# power_distribution_board_v4_final.net
KiCad netlist of a schematic drawn in EasyEDA
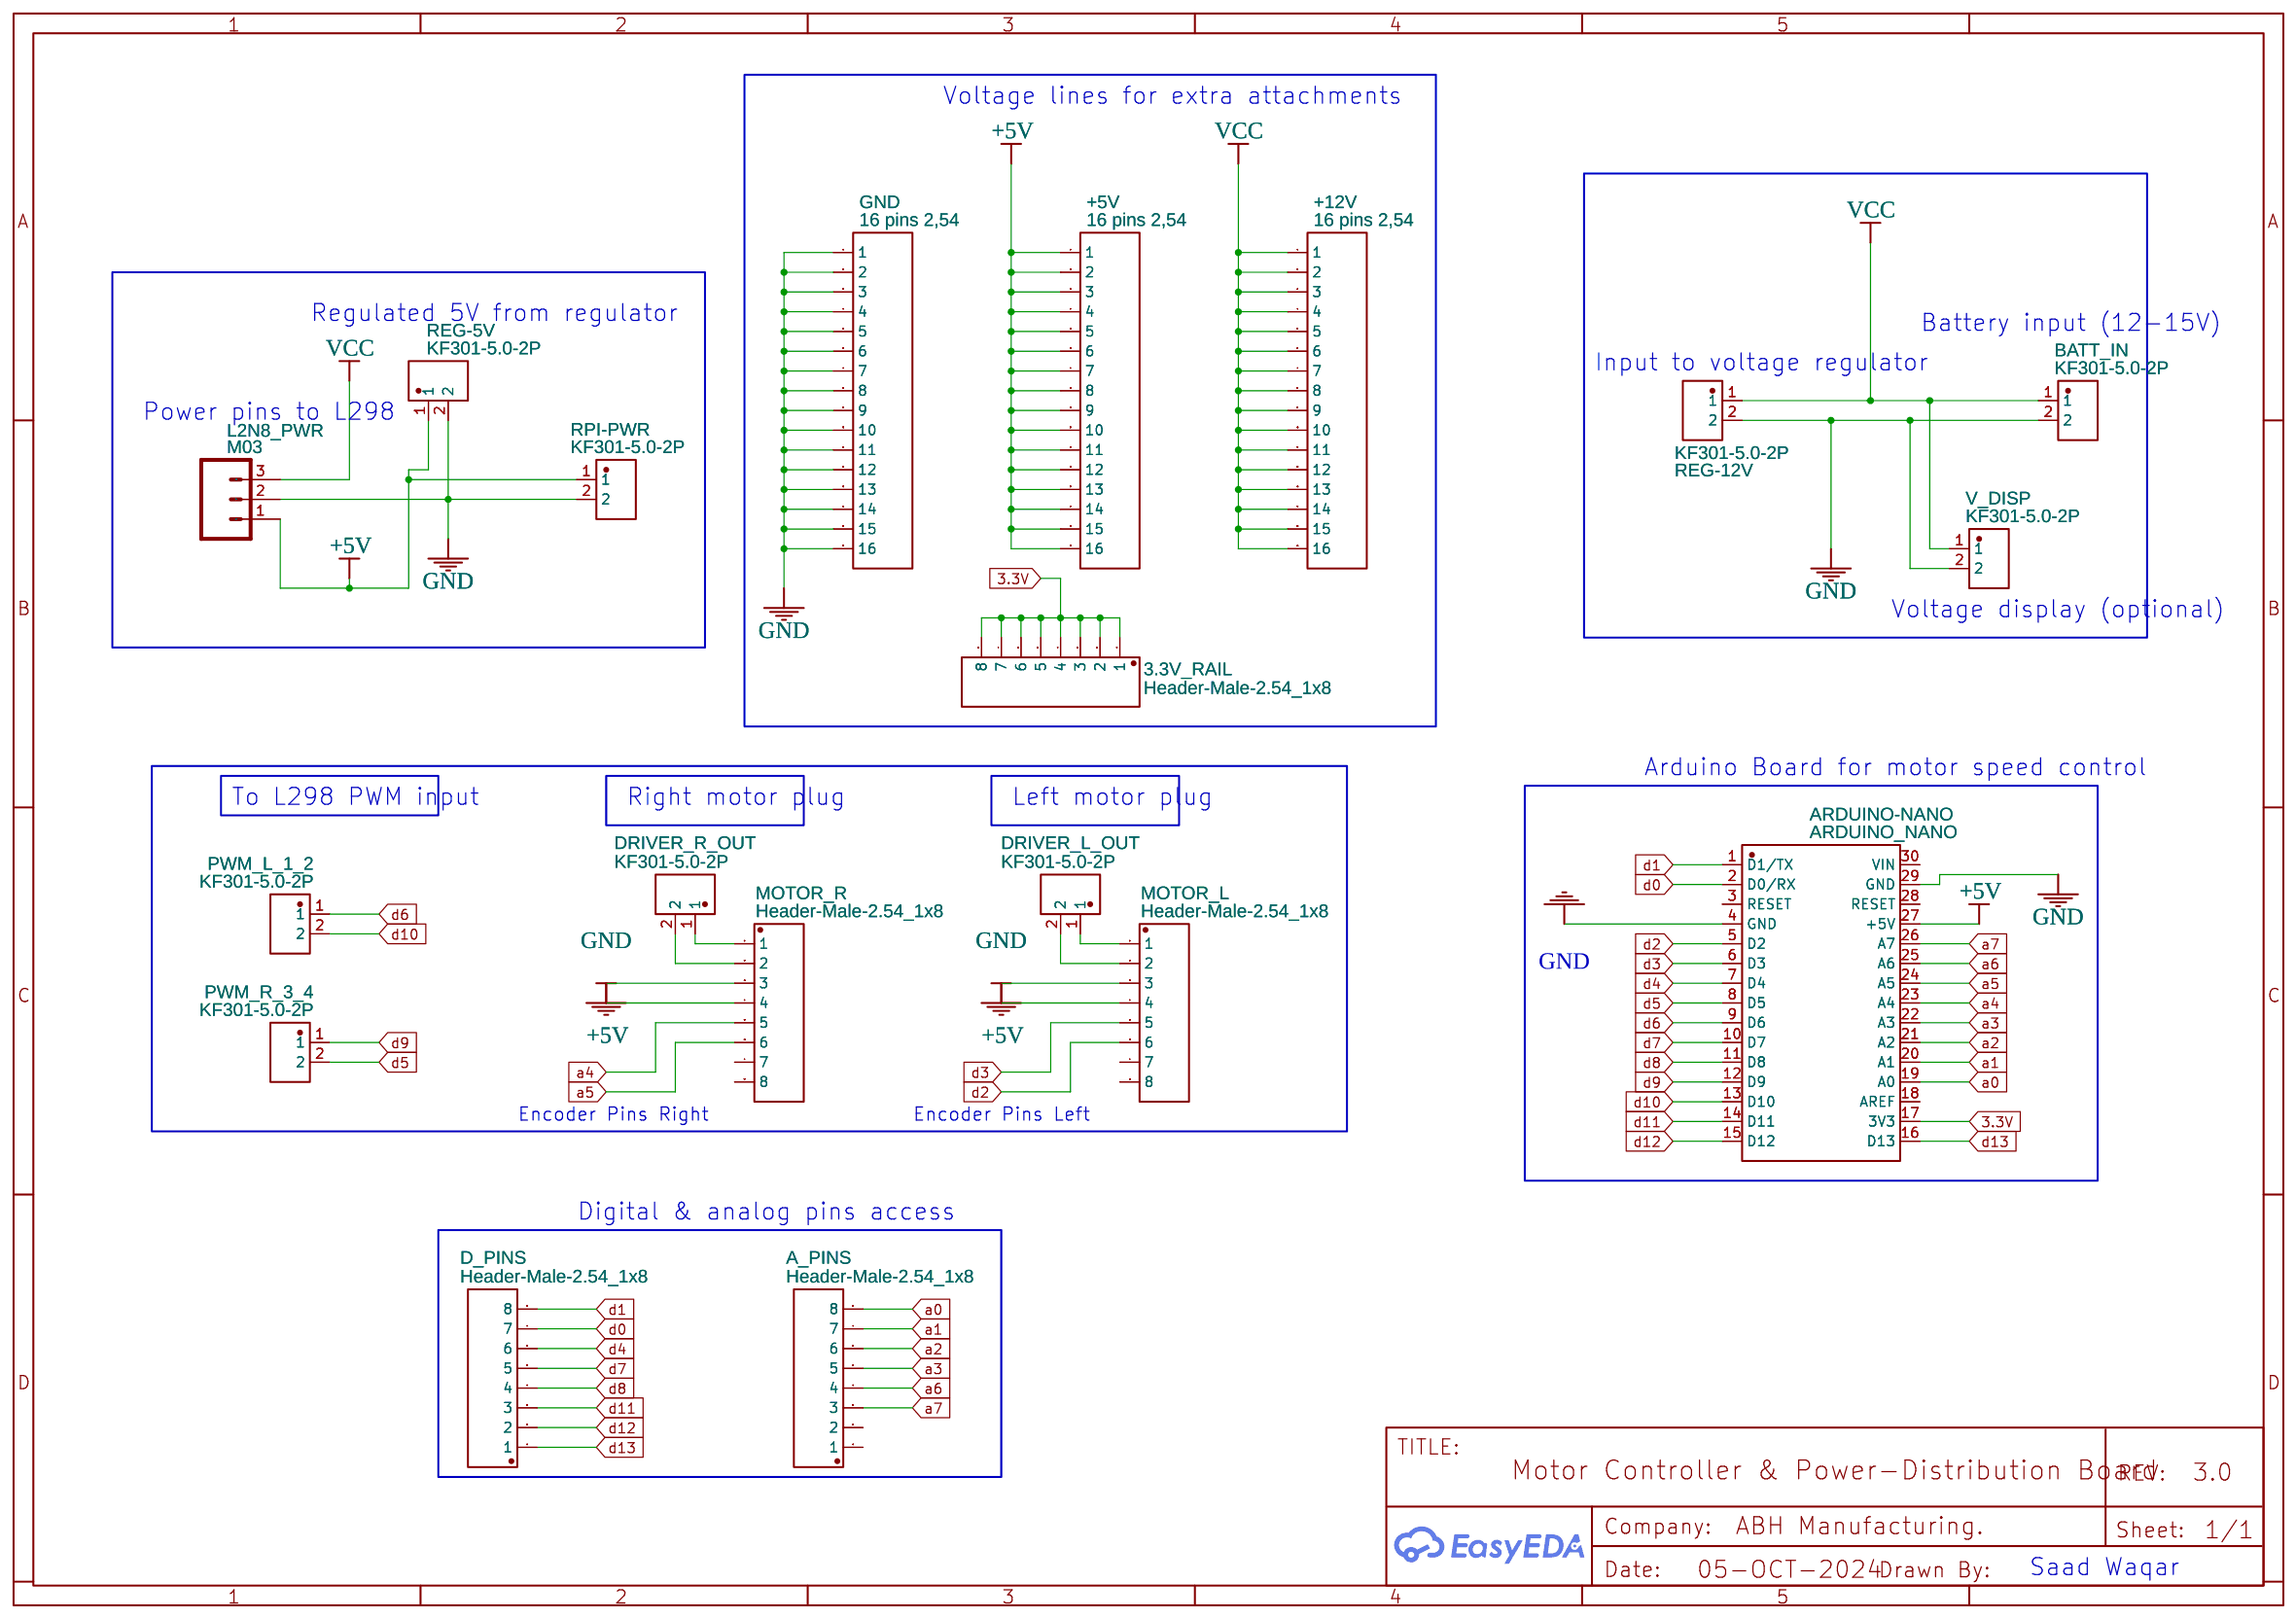
[diagram p0: schematic sheet]

(export (version "E")
  (design (tool "Eeschema 10.0.6"))
  (components
    (comp (ref "+5V") (value "16 pins 2,54") (libsource (lib "") (part "16 pins 2,54_2")))
    (comp (ref "+12V") (value "16 pins 2,54") (libsource (lib "") (part "16 pins 2,54_1")))
    (comp (ref "3.3V_RAIL")
      (value "Header-Male-2.54_1x8")
      (fields (field (name "Manufacturer Part") "B-2100S08P-A110") (field (name "Manufacturer") "Ckmtw(灿科盟)"))
      (libsource (lib "") (part "Header-Male-2.54_1x8_4"))
    )
    (comp (ref "ARDUINO-NANO") (value "ARDUINO_NANO") (libsource (lib "") (part "ARDUINO_NANO")))
    (comp (ref "A_PINS")
      (value "Header-Male-2.54_1x8")
      (fields (field (name "Manufacturer Part") "B-2100S08P-A110") (field (name "Manufacturer") "Ckmtw(灿科盟)"))
      (libsource (lib "") (part "Header-Male-2.54_1x8_1"))
    )
    (comp (ref "BATT_IN")
      (value "KF301-5.0-2P")
      (fields (field (name "Manufacturer") "KEFA(科发)"))
      (libsource (lib "") (part "KF301-5.0-2P_8"))
    )
    (comp (ref "DRIVER_L_OUT")
      (value "KF301-5.0-2P")
      (fields (field (name "Manufacturer") "KEFA(科发)"))
      (libsource (lib "") (part "KF301-5.0-2P_6"))
    )
    (comp (ref "DRIVER_R_OUT")
      (value "KF301-5.0-2P")
      (fields (field (name "Manufacturer") "KEFA(科发)"))
      (libsource (lib "") (part "KF301-5.0-2P"))
    )
    (comp (ref "D_PINS")
      (value "Header-Male-2.54_1x8")
      (fields (field (name "Manufacturer Part") "B-2100S08P-A110") (field (name "Manufacturer") "Ckmtw(灿科盟)"))
      (libsource (lib "") (part "Header-Male-2.54_1x8"))
    )
    (comp (ref "GND") (value "16 pins 2,54") (libsource (lib "") (part "16 pins 2,54")))
    (comp (ref "L2N8_PWR") (value "M03") (libsource (lib "") (part "M03")))
    (comp (ref "MOTOR_L")
      (value "Header-Male-2.54_1x8")
      (fields (field (name "Manufacturer Part") "B-2100S08P-A110") (field (name "Manufacturer") "Ckmtw(灿科盟)"))
      (libsource (lib "") (part "Header-Male-2.54_1x8_3"))
    )
    (comp (ref "MOTOR_R")
      (value "Header-Male-2.54_1x8")
      (fields (field (name "Manufacturer Part") "B-2100S08P-A110") (field (name "Manufacturer") "Ckmtw(灿科盟)"))
      (libsource (lib "") (part "Header-Male-2.54_1x8_2"))
    )
    (comp (ref "PWM_L_1_2")
      (value "KF301-5.0-2P")
      (fields (field (name "Manufacturer") "KEFA(科发)"))
      (libsource (lib "") (part "KF301-5.0-2P_7"))
    )
    (comp (ref "PWM_R_3_4")
      (value "KF301-5.0-2P")
      (fields (field (name "Manufacturer") "KEFA(科发)"))
      (libsource (lib "") (part "KF301-5.0-2P_3"))
    )
    (comp (ref "REG-5V")
      (value "KF301-5.0-2P")
      (fields (field (name "Manufacturer") "KEFA(科发)"))
      (libsource (lib "") (part "KF301-5.0-2P_2"))
    )
    (comp (ref "REG-12V")
      (value "KF301-5.0-2P")
      (fields (field (name "Manufacturer") "KEFA(科发)"))
      (libsource (lib "") (part "KF301-5.0-2P_4"))
    )
    (comp (ref "RPI-PWR")
      (value "KF301-5.0-2P")
      (fields (field (name "Manufacturer") "KEFA(科发)"))
      (libsource (lib "") (part "KF301-5.0-2P_1"))
    )
    (comp (ref "V_DISP")
      (value "KF301-5.0-2P")
      (fields (field (name "Manufacturer") "KEFA(科发)"))
      (libsource (lib "") (part "KF301-5.0-2P_5"))
    )
  )
  (nets
    (net (code "1") (name "+5V") (class "Default")
      (node (ref "+5V") (pin "1") (pinfunction "1_1") (pintype "input"))
      (node (ref "+5V") (pin "10") (pinfunction "10_10") (pintype "input"))
      (node (ref "+5V") (pin "11") (pinfunction "11_11") (pintype "input"))
      (node (ref "+5V") (pin "12") (pinfunction "12_12") (pintype "input"))
      (node (ref "+5V") (pin "13") (pinfunction "13_13") (pintype "input"))
      (node (ref "+5V") (pin "14") (pinfunction "14_14") (pintype "input"))
      (node (ref "+5V") (pin "15") (pinfunction "15_15") (pintype "input"))
      (node (ref "+5V") (pin "16") (pinfunction "16_16") (pintype "input"))
      (node (ref "+5V") (pin "2") (pinfunction "2_2") (pintype "input"))
      (node (ref "+5V") (pin "3") (pinfunction "3_3") (pintype "input"))
      (node (ref "+5V") (pin "4") (pinfunction "4_4") (pintype "input"))
      (node (ref "+5V") (pin "5") (pinfunction "5_5") (pintype "input"))
      (node (ref "+5V") (pin "6") (pinfunction "6_6") (pintype "input"))
      (node (ref "+5V") (pin "7") (pinfunction "7_7") (pintype "input"))
      (node (ref "+5V") (pin "8") (pinfunction "8_8") (pintype "input"))
      (node (ref "+5V") (pin "9") (pinfunction "9_9") (pintype "input"))
      (node (ref "ARDUINO-NANO") (pin "27") (pinfunction "+5V_27") (pintype "unspecified"))
      (node (ref "L2N8_PWR") (pin "1") (pinfunction "1_1") (pintype "unspecified"))
      (node (ref "MOTOR_L") (pin "4") (pinfunction "4_4") (pintype "unspecified"))
      (node (ref "MOTOR_R") (pin "4") (pinfunction "4_4") (pintype "unspecified"))
      (node (ref "REG-5V") (pin "1") (pinfunction "1_1") (pintype "unspecified"))
      (node (ref "RPI-PWR") (pin "1") (pinfunction "1_1") (pintype "unspecified"))
    )
    (net (code "2") (name "3.3V") (class "Default")
      (node (ref "3.3V_RAIL") (pin "1") (pinfunction "1_1") (pintype "unspecified"))
      (node (ref "3.3V_RAIL") (pin "2") (pinfunction "2_2") (pintype "unspecified"))
      (node (ref "3.3V_RAIL") (pin "3") (pinfunction "3_3") (pintype "unspecified"))
      (node (ref "3.3V_RAIL") (pin "4") (pinfunction "4_4") (pintype "unspecified"))
      (node (ref "3.3V_RAIL") (pin "5") (pinfunction "5_5") (pintype "unspecified"))
      (node (ref "3.3V_RAIL") (pin "6") (pinfunction "6_6") (pintype "unspecified"))
      (node (ref "3.3V_RAIL") (pin "7") (pinfunction "7_7") (pintype "unspecified"))
      (node (ref "3.3V_RAIL") (pin "8") (pinfunction "8_8") (pintype "unspecified"))
      (node (ref "ARDUINO-NANO") (pin "17") (pinfunction "3V3_17") (pintype "unspecified"))
    )
    (net (code "3") (name "GND") (class "Default")
      (node (ref "ARDUINO-NANO") (pin "29") (pinfunction "GND_29") (pintype "unspecified"))
      (node (ref "ARDUINO-NANO") (pin "4") (pinfunction "GND_4") (pintype "unspecified"))
      (node (ref "BATT_IN") (pin "2") (pinfunction "2_2") (pintype "unspecified"))
      (node (ref "GND") (pin "1") (pinfunction "1_1") (pintype "input"))
      (node (ref "GND") (pin "10") (pinfunction "10_10") (pintype "input"))
      (node (ref "GND") (pin "11") (pinfunction "11_11") (pintype "input"))
      (node (ref "GND") (pin "12") (pinfunction "12_12") (pintype "input"))
      (node (ref "GND") (pin "13") (pinfunction "13_13") (pintype "input"))
      (node (ref "GND") (pin "14") (pinfunction "14_14") (pintype "input"))
      (node (ref "GND") (pin "15") (pinfunction "15_15") (pintype "input"))
      (node (ref "GND") (pin "16") (pinfunction "16_16") (pintype "input"))
      (node (ref "GND") (pin "2") (pinfunction "2_2") (pintype "input"))
      (node (ref "GND") (pin "3") (pinfunction "3_3") (pintype "input"))
      (node (ref "GND") (pin "4") (pinfunction "4_4") (pintype "input"))
      (node (ref "GND") (pin "5") (pinfunction "5_5") (pintype "input"))
      (node (ref "GND") (pin "6") (pinfunction "6_6") (pintype "input"))
      (node (ref "GND") (pin "7") (pinfunction "7_7") (pintype "input"))
      (node (ref "GND") (pin "8") (pinfunction "8_8") (pintype "input"))
      (node (ref "GND") (pin "9") (pinfunction "9_9") (pintype "input"))
      (node (ref "L2N8_PWR") (pin "2") (pinfunction "2_2") (pintype "unspecified"))
      (node (ref "MOTOR_L") (pin "3") (pinfunction "3_3") (pintype "unspecified"))
      (node (ref "MOTOR_R") (pin "3") (pinfunction "3_3") (pintype "unspecified"))
      (node (ref "REG-12V") (pin "2") (pinfunction "2_2") (pintype "unspecified"))
      (node (ref "REG-5V") (pin "2") (pinfunction "2_2") (pintype "unspecified"))
      (node (ref "RPI-PWR") (pin "2") (pinfunction "2_2") (pintype "unspecified"))
      (node (ref "V_DISP") (pin "2") (pinfunction "2_2") (pintype "unspecified"))
    )
    (net (code "4") (name "Net-(DRIVER_L_OUT-Pad1)") (class "Default")
      (node (ref "DRIVER_L_OUT") (pin "1") (pinfunction "1_1") (pintype "unspecified"))
      (node (ref "MOTOR_L") (pin "1") (pinfunction "1_1") (pintype "unspecified"))
    )
    (net (code "5") (name "Net-(DRIVER_L_OUT-Pad2)") (class "Default")
      (node (ref "DRIVER_L_OUT") (pin "2") (pinfunction "2_2") (pintype "unspecified"))
      (node (ref "MOTOR_L") (pin "2") (pinfunction "2_2") (pintype "unspecified"))
    )
    (net (code "6") (name "Net-(DRIVER_R_OUT-Pad1)") (class "Default")
      (node (ref "DRIVER_R_OUT") (pin "1") (pinfunction "1_1") (pintype "unspecified"))
      (node (ref "MOTOR_R") (pin "1") (pinfunction "1_1") (pintype "unspecified"))
    )
    (net (code "7") (name "Net-(DRIVER_R_OUT-Pad2)") (class "Default")
      (node (ref "DRIVER_R_OUT") (pin "2") (pinfunction "2_2") (pintype "unspecified"))
      (node (ref "MOTOR_R") (pin "2") (pinfunction "2_2") (pintype "unspecified"))
    )
    (net (code "8") (name "VCC") (class "Default")
      (node (ref "+12V") (pin "1") (pinfunction "1_1") (pintype "input"))
      (node (ref "+12V") (pin "10") (pinfunction "10_10") (pintype "input"))
      (node (ref "+12V") (pin "11") (pinfunction "11_11") (pintype "input"))
      (node (ref "+12V") (pin "12") (pinfunction "12_12") (pintype "input"))
      (node (ref "+12V") (pin "13") (pinfunction "13_13") (pintype "input"))
      (node (ref "+12V") (pin "14") (pinfunction "14_14") (pintype "input"))
      (node (ref "+12V") (pin "15") (pinfunction "15_15") (pintype "input"))
      (node (ref "+12V") (pin "16") (pinfunction "16_16") (pintype "input"))
      (node (ref "+12V") (pin "2") (pinfunction "2_2") (pintype "input"))
      (node (ref "+12V") (pin "3") (pinfunction "3_3") (pintype "input"))
      (node (ref "+12V") (pin "4") (pinfunction "4_4") (pintype "input"))
      (node (ref "+12V") (pin "5") (pinfunction "5_5") (pintype "input"))
      (node (ref "+12V") (pin "6") (pinfunction "6_6") (pintype "input"))
      (node (ref "+12V") (pin "7") (pinfunction "7_7") (pintype "input"))
      (node (ref "+12V") (pin "8") (pinfunction "8_8") (pintype "input"))
      (node (ref "+12V") (pin "9") (pinfunction "9_9") (pintype "input"))
      (node (ref "BATT_IN") (pin "1") (pinfunction "1_1") (pintype "unspecified"))
      (node (ref "L2N8_PWR") (pin "3") (pinfunction "3_3") (pintype "unspecified"))
      (node (ref "REG-12V") (pin "1") (pinfunction "1_1") (pintype "unspecified"))
      (node (ref "V_DISP") (pin "1") (pinfunction "1_1") (pintype "unspecified"))
    )
    (net (code "9") (name "a0") (class "Default")
      (node (ref "ARDUINO-NANO") (pin "19") (pinfunction "A0_19") (pintype "unspecified"))
      (node (ref "A_PINS") (pin "8") (pinfunction "8_8") (pintype "unspecified"))
    )
    (net (code "10") (name "a1") (class "Default")
      (node (ref "ARDUINO-NANO") (pin "20") (pinfunction "A1_20") (pintype "unspecified"))
      (node (ref "A_PINS") (pin "7") (pinfunction "7_7") (pintype "unspecified"))
    )
    (net (code "11") (name "a2") (class "Default")
      (node (ref "ARDUINO-NANO") (pin "21") (pinfunction "A2_21") (pintype "unspecified"))
      (node (ref "A_PINS") (pin "6") (pinfunction "6_6") (pintype "unspecified"))
    )
    (net (code "12") (name "a3") (class "Default")
      (node (ref "ARDUINO-NANO") (pin "22") (pinfunction "A3_22") (pintype "unspecified"))
      (node (ref "A_PINS") (pin "5") (pinfunction "5_5") (pintype "unspecified"))
    )
    (net (code "13") (name "a4") (class "Default")
      (node (ref "ARDUINO-NANO") (pin "23") (pinfunction "A4_23") (pintype "unspecified"))
      (node (ref "MOTOR_R") (pin "5") (pinfunction "5_5") (pintype "unspecified"))
    )
    (net (code "14") (name "a5") (class "Default")
      (node (ref "ARDUINO-NANO") (pin "24") (pinfunction "A5_24") (pintype "unspecified"))
      (node (ref "MOTOR_R") (pin "6") (pinfunction "6_6") (pintype "unspecified"))
    )
    (net (code "15") (name "a6") (class "Default")
      (node (ref "ARDUINO-NANO") (pin "25") (pinfunction "A6_25") (pintype "unspecified"))
      (node (ref "A_PINS") (pin "4") (pinfunction "4_4") (pintype "unspecified"))
    )
    (net (code "16") (name "a7") (class "Default")
      (node (ref "ARDUINO-NANO") (pin "26") (pinfunction "A7_26") (pintype "unspecified"))
      (node (ref "A_PINS") (pin "3") (pinfunction "3_3") (pintype "unspecified"))
    )
    (net (code "17") (name "d0") (class "Default")
      (node (ref "ARDUINO-NANO") (pin "2") (pinfunction "D0/RX_2") (pintype "unspecified"))
      (node (ref "D_PINS") (pin "7") (pinfunction "7_7") (pintype "unspecified"))
    )
    (net (code "18") (name "d1") (class "Default")
      (node (ref "ARDUINO-NANO") (pin "1") (pinfunction "D1/TX_1") (pintype "unspecified"))
      (node (ref "D_PINS") (pin "8") (pinfunction "8_8") (pintype "unspecified"))
    )
    (net (code "19") (name "d2") (class "Default")
      (node (ref "ARDUINO-NANO") (pin "5") (pinfunction "D2_5") (pintype "unspecified"))
      (node (ref "MOTOR_L") (pin "6") (pinfunction "6_6") (pintype "unspecified"))
    )
    (net (code "20") (name "d3") (class "Default")
      (node (ref "ARDUINO-NANO") (pin "6") (pinfunction "D3_6") (pintype "unspecified"))
      (node (ref "MOTOR_L") (pin "5") (pinfunction "5_5") (pintype "unspecified"))
    )
    (net (code "21") (name "d4") (class "Default")
      (node (ref "ARDUINO-NANO") (pin "7") (pinfunction "D4_7") (pintype "unspecified"))
      (node (ref "D_PINS") (pin "6") (pinfunction "6_6") (pintype "unspecified"))
    )
    (net (code "22") (name "d5") (class "Default")
      (node (ref "ARDUINO-NANO") (pin "8") (pinfunction "D5_8") (pintype "unspecified"))
      (node (ref "PWM_R_3_4") (pin "2") (pinfunction "2_2") (pintype "unspecified"))
    )
    (net (code "23") (name "d6") (class "Default")
      (node (ref "ARDUINO-NANO") (pin "9") (pinfunction "D6_9") (pintype "unspecified"))
      (node (ref "PWM_L_1_2") (pin "1") (pinfunction "1_1") (pintype "unspecified"))
    )
    (net (code "24") (name "d7") (class "Default")
      (node (ref "ARDUINO-NANO") (pin "10") (pinfunction "D7_10") (pintype "unspecified"))
      (node (ref "D_PINS") (pin "5") (pinfunction "5_5") (pintype "unspecified"))
    )
    (net (code "25") (name "d8") (class "Default")
      (node (ref "ARDUINO-NANO") (pin "11") (pinfunction "D8_11") (pintype "unspecified"))
      (node (ref "D_PINS") (pin "4") (pinfunction "4_4") (pintype "unspecified"))
    )
    (net (code "26") (name "d9") (class "Default")
      (node (ref "ARDUINO-NANO") (pin "12") (pinfunction "D9_12") (pintype "unspecified"))
      (node (ref "PWM_R_3_4") (pin "1") (pinfunction "1_1") (pintype "unspecified"))
    )
    (net (code "27") (name "d10") (class "Default")
      (node (ref "ARDUINO-NANO") (pin "13") (pinfunction "D10_13") (pintype "unspecified"))
      (node (ref "PWM_L_1_2") (pin "2") (pinfunction "2_2") (pintype "unspecified"))
    )
    (net (code "28") (name "d11") (class "Default")
      (node (ref "ARDUINO-NANO") (pin "14") (pinfunction "D11_14") (pintype "unspecified"))
      (node (ref "D_PINS") (pin "3") (pinfunction "3_3") (pintype "unspecified"))
    )
    (net (code "29") (name "d12") (class "Default")
      (node (ref "ARDUINO-NANO") (pin "15") (pinfunction "D12_15") (pintype "unspecified"))
      (node (ref "D_PINS") (pin "2") (pinfunction "2_2") (pintype "unspecified"))
    )
    (net (code "30") (name "d13") (class "Default")
      (node (ref "ARDUINO-NANO") (pin "16") (pinfunction "D13_16") (pintype "unspecified"))
      (node (ref "D_PINS") (pin "1") (pinfunction "1_1") (pintype "unspecified"))
    )
    (net (code "31") (name "unconnected-(ARDUINO-NANO-AREF-Pad18)") (class "Default")
      (node (ref "ARDUINO-NANO") (pin "18") (pinfunction "AREF_18") (pintype "unspecified"))
    )
    (net (code "32") (name "unconnected-(ARDUINO-NANO-RESET-Pad3)") (class "Default")
      (node (ref "ARDUINO-NANO") (pin "3") (pinfunction "RESET_3") (pintype "unspecified"))
    )
    (net (code "33") (name "unconnected-(ARDUINO-NANO-RESET-Pad28)") (class "Default")
      (node (ref "ARDUINO-NANO") (pin "28") (pinfunction "RESET_28") (pintype "unspecified"))
    )
    (net (code "34") (name "unconnected-(ARDUINO-NANO-VIN-Pad30)") (class "Default")
      (node (ref "ARDUINO-NANO") (pin "30") (pinfunction "VIN_30") (pintype "unspecified"))
    )
    (net (code "35") (name "unconnected-(A_PINS-Pad1)") (class "Default")
      (node (ref "A_PINS") (pin "1") (pinfunction "1_1") (pintype "unspecified"))
    )
    (net (code "36") (name "unconnected-(A_PINS-Pad2)") (class "Default")
      (node (ref "A_PINS") (pin "2") (pinfunction "2_2") (pintype "unspecified"))
    )
    (net (code "37") (name "unconnected-(MOTOR_L-Pad7)") (class "Default")
      (node (ref "MOTOR_L") (pin "7") (pinfunction "7_7") (pintype "unspecified"))
    )
    (net (code "38") (name "unconnected-(MOTOR_L-Pad8)") (class "Default")
      (node (ref "MOTOR_L") (pin "8") (pinfunction "8_8") (pintype "unspecified"))
    )
    (net (code "39") (name "unconnected-(MOTOR_R-Pad7)") (class "Default")
      (node (ref "MOTOR_R") (pin "7") (pinfunction "7_7") (pintype "unspecified"))
    )
    (net (code "40") (name "unconnected-(MOTOR_R-Pad8)") (class "Default")
      (node (ref "MOTOR_R") (pin "8") (pinfunction "8_8") (pintype "unspecified"))
    )
  )
)
